# Main_Board.net
KiCad netlist of a schematic drawn in EAGLE
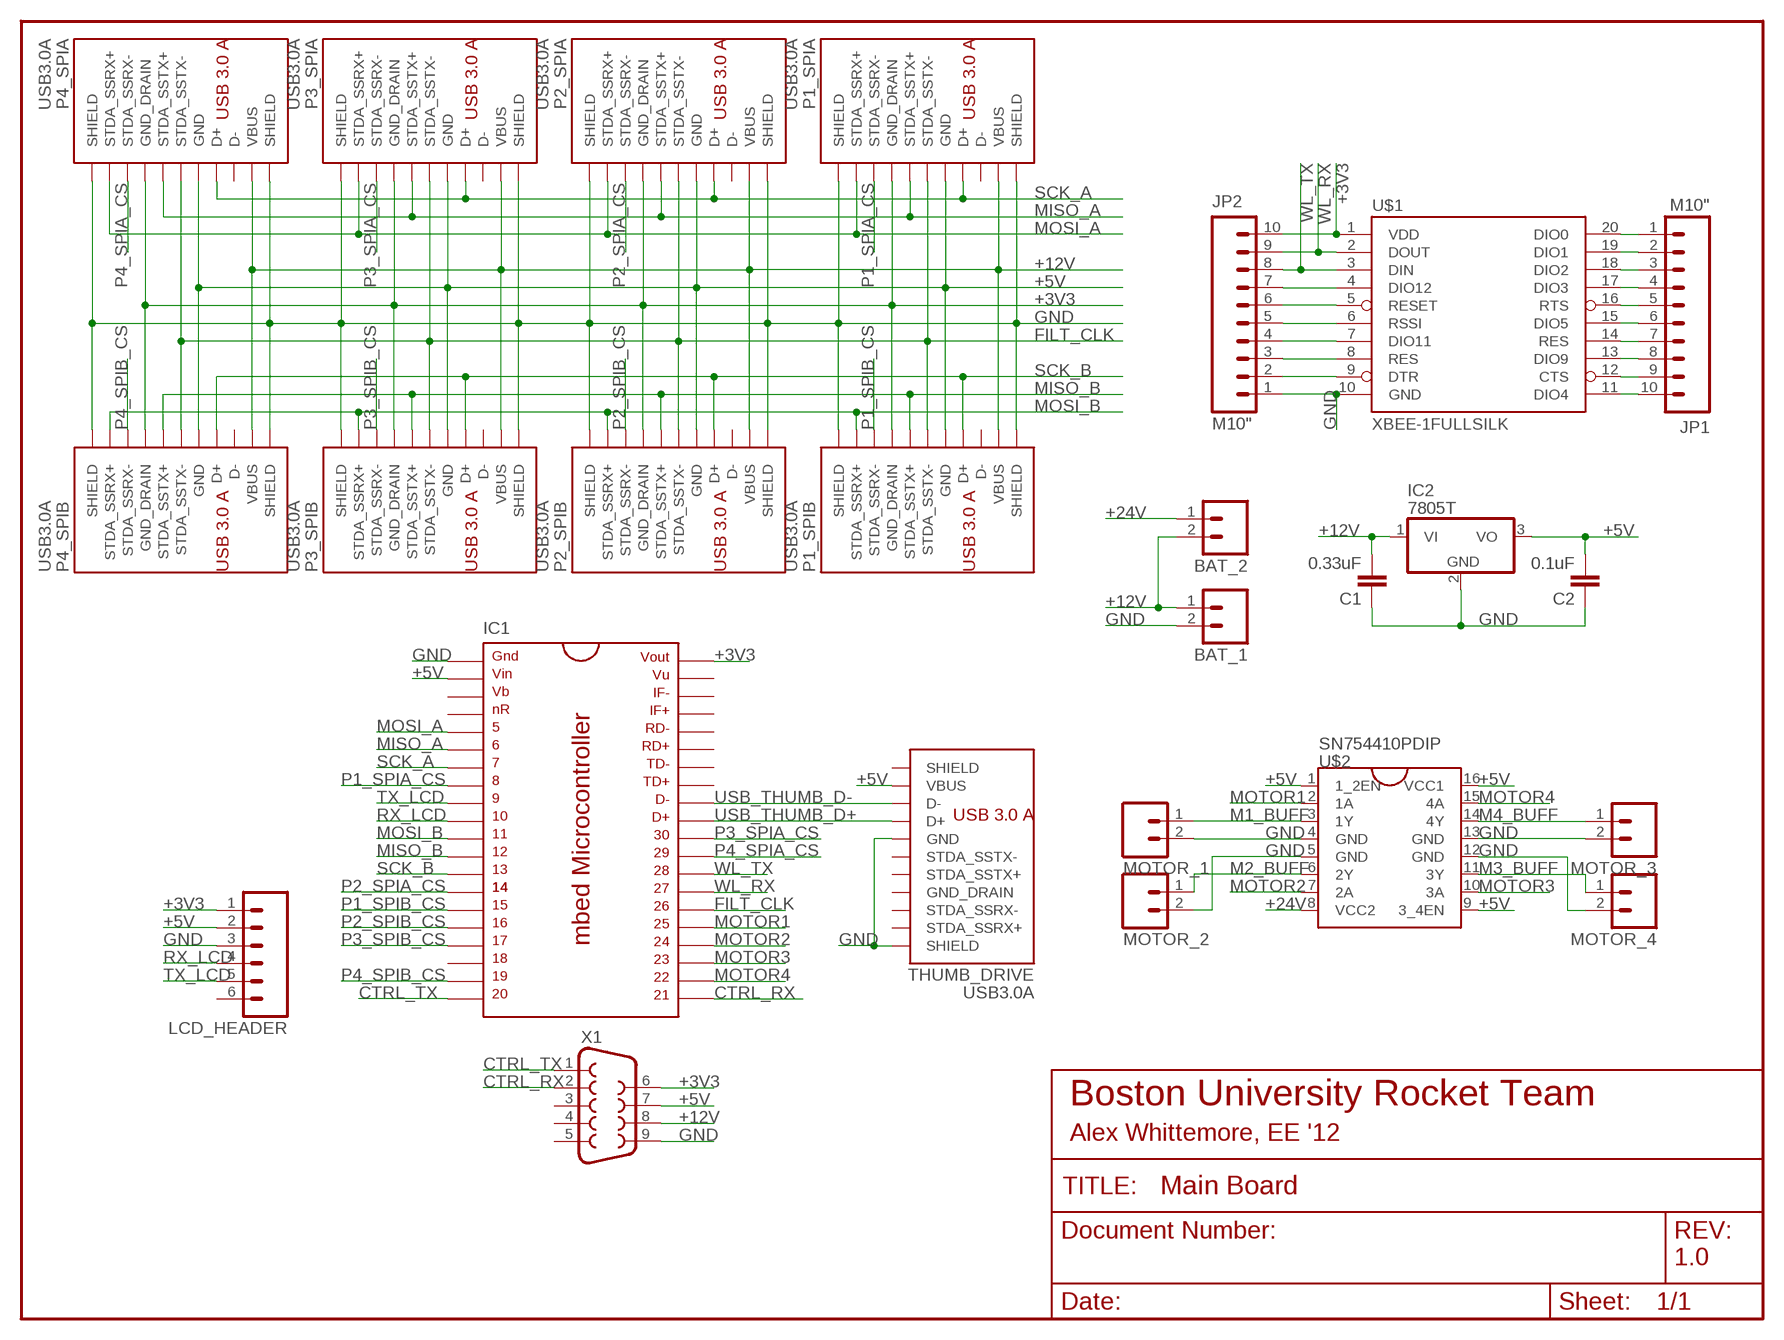
[diagram p0: schematic, sheet 1]

(export (version "E")
  (design (tool "Eeschema 10.0.6"))
  (components
    (comp (ref "BAT_1")
      (value "M025MM")
      (footprint "eagle-import:SCREWTERMINAL-5MM-2")
      (libsource (lib "eagle-import") (part "M025MM"))
    )
    (comp (ref "BAT_2")
      (value "M025MM")
      (footprint "eagle-import:SCREWTERMINAL-5MM-2")
      (libsource (lib "eagle-import") (part "M025MM"))
    )
    (comp (ref "C1")
      (value "0.33uF")
      (footprint "eagle-import:0402-CAP")
      (libsource (lib "eagle-import") (part "CAP0402-CAP"))
    )
    (comp (ref "C2")
      (value "0.1uF")
      (footprint "eagle-import:0402-CAP")
      (libsource (lib "eagle-import") (part "CAP0402-CAP"))
    )
    (comp (ref "IC1")
      (value "MBED_MICROCONTROLLER")
      (footprint "eagle-import:DIL40_0.9")
      (libsource (lib "eagle-import") (part "MBED_MICROCONTROLLER"))
    )
    (comp (ref "IC2")
      (value "7805T")
      (footprint "eagle-import:TO220H")
      (libsource (lib "eagle-import") (part "78T05"))
    )
    (comp (ref "JP1")
      (value "M10\"")
      (footprint "eagle-import:1X10")
      (libsource (lib "eagle-import") (part "M10{dblquote}"))
    )
    (comp (ref "JP2")
      (value "M10\"")
      (footprint "eagle-import:1X10")
      (libsource (lib "eagle-import") (part "M10{dblquote}"))
    )
    (comp (ref "LCD_HEADER")
      (value "M06LOCK")
      (footprint "eagle-import:1X06_LOCK")
      (libsource (lib "eagle-import") (part "M06LOCK"))
    )
    (comp (ref "MOTOR_1")
      (value "M025MM")
      (footprint "eagle-import:SCREWTERMINAL-5MM-2")
      (libsource (lib "eagle-import") (part "M025MM"))
    )
    (comp (ref "MOTOR_2")
      (value "M025MM")
      (footprint "eagle-import:SCREWTERMINAL-5MM-2")
      (libsource (lib "eagle-import") (part "M025MM"))
    )
    (comp (ref "MOTOR_3")
      (value "M025MM")
      (footprint "eagle-import:SCREWTERMINAL-5MM-2")
      (libsource (lib "eagle-import") (part "M025MM"))
    )
    (comp (ref "MOTOR_4")
      (value "M025MM")
      (footprint "eagle-import:SCREWTERMINAL-5MM-2")
      (libsource (lib "eagle-import") (part "M025MM"))
    )
    (comp (ref "P1_SPIA")
      (value "USB3.0A")
      (footprint "eagle-import:AMPHENOLUSB3.0A")
      (libsource (lib "eagle-import") (part "USB3.0A"))
    )
    (comp (ref "P1_SPIB")
      (value "USB3.0A")
      (footprint "eagle-import:AMPHENOLUSB3.0A")
      (libsource (lib "eagle-import") (part "USB3.0A"))
    )
    (comp (ref "P2_SPIA")
      (value "USB3.0A")
      (footprint "eagle-import:AMPHENOLUSB3.0A")
      (libsource (lib "eagle-import") (part "USB3.0A"))
    )
    (comp (ref "P2_SPIB")
      (value "USB3.0A")
      (footprint "eagle-import:AMPHENOLUSB3.0A")
      (libsource (lib "eagle-import") (part "USB3.0A"))
    )
    (comp (ref "P3_SPIA")
      (value "USB3.0A")
      (footprint "eagle-import:AMPHENOLUSB3.0A")
      (libsource (lib "eagle-import") (part "USB3.0A"))
    )
    (comp (ref "P3_SPIB")
      (value "USB3.0A")
      (footprint "eagle-import:AMPHENOLUSB3.0A")
      (libsource (lib "eagle-import") (part "USB3.0A"))
    )
    (comp (ref "P4_SPIA")
      (value "USB3.0A")
      (footprint "eagle-import:AMPHENOLUSB3.0A")
      (libsource (lib "eagle-import") (part "USB3.0A"))
    )
    (comp (ref "P4_SPIB")
      (value "USB3.0A")
      (footprint "eagle-import:AMPHENOLUSB3.0A")
      (libsource (lib "eagle-import") (part "USB3.0A"))
    )
    (comp (ref "THUMB_DRIVE")
      (value "USB3.0A")
      (footprint "eagle-import:AMPHENOLUSB3.0A")
      (libsource (lib "eagle-import") (part "USB3.0A"))
    )
    (comp (ref "U$1")
      (value "XBEE-1FULLSILK")
      (footprint "eagle-import:XBEE")
      (libsource (lib "eagle-import") (part "XBEE-1FULLSILK"))
    )
    (comp (ref "U$2")
      (value "SN754410PDIP")
      (footprint "eagle-import:DIL16")
      (libsource (lib "eagle-import") (part "SN754410PDIP"))
    )
    (comp (ref "X1")
      (value "DB9MALE")
      (footprint "eagle-import:DB9_MALE")
      (libsource (lib "eagle-import") (part "DB9MALE"))
    )
  )
  (nets
    (net (code "1") (name "/+3V3") (class "Default")
      (node (ref "IC1") (pin "40") (pinfunction "P$40_40") (pintype "bidirectional"))
      (node (ref "JP2") (pin "10") (pinfunction "10_10") (pintype "passive"))
      (node (ref "LCD_HEADER") (pin "1") (pinfunction "1_1") (pintype "passive"))
      (node (ref "P1_SPIA") (pin "7") (pinfunction "GND_DRAIN_7") (pintype "bidirectional"))
      (node (ref "P1_SPIB") (pin "7") (pinfunction "GND_DRAIN_7") (pintype "bidirectional"))
      (node (ref "P2_SPIA") (pin "7") (pinfunction "GND_DRAIN_7") (pintype "bidirectional"))
      (node (ref "P2_SPIB") (pin "7") (pinfunction "GND_DRAIN_7") (pintype "bidirectional"))
      (node (ref "P3_SPIA") (pin "7") (pinfunction "GND_DRAIN_7") (pintype "bidirectional"))
      (node (ref "P3_SPIB") (pin "7") (pinfunction "GND_DRAIN_7") (pintype "bidirectional"))
      (node (ref "P4_SPIA") (pin "7") (pinfunction "GND_DRAIN_7") (pintype "bidirectional"))
      (node (ref "P4_SPIB") (pin "7") (pinfunction "GND_DRAIN_7") (pintype "bidirectional"))
      (node (ref "U$1") (pin "1") (pinfunction "VDD_1") (pintype "power_in"))
      (node (ref "X1") (pin "6") (pinfunction "6_6") (pintype "passive"))
    )
    (net (code "2") (name "/+5V") (class "Default")
      (node (ref "C2") (pin "2") (pinfunction "2_2") (pintype "passive"))
      (node (ref "IC1") (pin "2") (pinfunction "P$2_2") (pintype "bidirectional"))
      (node (ref "IC2") (pin "3") (pinfunction "VO_3") (pintype "passive"))
      (node (ref "LCD_HEADER") (pin "2") (pinfunction "2_2") (pintype "passive"))
      (node (ref "P1_SPIA") (pin "4") (pinfunction "GND_4") (pintype "bidirectional"))
      (node (ref "P1_SPIB") (pin "4") (pinfunction "GND_4") (pintype "bidirectional"))
      (node (ref "P2_SPIA") (pin "4") (pinfunction "GND_4") (pintype "bidirectional"))
      (node (ref "P2_SPIB") (pin "4") (pinfunction "GND_4") (pintype "bidirectional"))
      (node (ref "P3_SPIA") (pin "4") (pinfunction "GND_4") (pintype "bidirectional"))
      (node (ref "P3_SPIB") (pin "4") (pinfunction "GND_4") (pintype "bidirectional"))
      (node (ref "P4_SPIA") (pin "4") (pinfunction "GND_4") (pintype "bidirectional"))
      (node (ref "P4_SPIB") (pin "4") (pinfunction "GND_4") (pintype "bidirectional"))
      (node (ref "THUMB_DRIVE") (pin "1") (pinfunction "VBUS_1") (pintype "bidirectional"))
      (node (ref "U$2") (pin "1") (pinfunction "1_2EN_1") (pintype "bidirectional"))
      (node (ref "U$2") (pin "16") (pinfunction "VCC1_16") (pintype "bidirectional"))
      (node (ref "U$2") (pin "9") (pinfunction "3_4EN_9") (pintype "bidirectional"))
      (node (ref "X1") (pin "7") (pinfunction "7_7") (pintype "passive"))
    )
    (net (code "3") (name "/+12V") (class "Default")
      (node (ref "BAT_1") (pin "1") (pinfunction "1_1") (pintype "passive"))
      (node (ref "BAT_2") (pin "2") (pinfunction "2_2") (pintype "passive"))
      (node (ref "C1") (pin "2") (pinfunction "2_2") (pintype "passive"))
      (node (ref "IC2") (pin "1") (pinfunction "VI_1") (pintype "input"))
      (node (ref "P1_SPIA") (pin "1") (pinfunction "VBUS_1") (pintype "bidirectional"))
      (node (ref "P1_SPIB") (pin "1") (pinfunction "VBUS_1") (pintype "bidirectional"))
      (node (ref "P2_SPIA") (pin "1") (pinfunction "VBUS_1") (pintype "bidirectional"))
      (node (ref "P2_SPIB") (pin "1") (pinfunction "VBUS_1") (pintype "bidirectional"))
      (node (ref "P3_SPIA") (pin "1") (pinfunction "VBUS_1") (pintype "bidirectional"))
      (node (ref "P3_SPIB") (pin "1") (pinfunction "VBUS_1") (pintype "bidirectional"))
      (node (ref "P4_SPIA") (pin "1") (pinfunction "VBUS_1") (pintype "bidirectional"))
      (node (ref "P4_SPIB") (pin "1") (pinfunction "VBUS_1") (pintype "bidirectional"))
      (node (ref "X1") (pin "8") (pinfunction "8_8") (pintype "passive"))
    )
    (net (code "4") (name "/+24V") (class "Default")
      (node (ref "BAT_2") (pin "1") (pinfunction "1_1") (pintype "passive"))
      (node (ref "U$2") (pin "8") (pinfunction "VCC2_8") (pintype "bidirectional"))
    )
    (net (code "5") (name "/CTRL_RX") (class "Default")
      (node (ref "IC1") (pin "21") (pinfunction "P$21_21") (pintype "bidirectional"))
      (node (ref "X1") (pin "2") (pinfunction "2_2") (pintype "passive"))
    )
    (net (code "6") (name "/CTRL_TX") (class "Default")
      (node (ref "IC1") (pin "20") (pinfunction "P$20_20") (pintype "bidirectional"))
      (node (ref "X1") (pin "1") (pinfunction "1_1") (pintype "passive"))
    )
    (net (code "7") (name "/FILT_CLK") (class "Default")
      (node (ref "IC1") (pin "26") (pinfunction "P$26_26") (pintype "bidirectional"))
      (node (ref "P1_SPIA") (pin "8") (pinfunction "STDA_SSTX-_8") (pintype "bidirectional"))
      (node (ref "P1_SPIB") (pin "8") (pinfunction "STDA_SSTX-_8") (pintype "bidirectional"))
      (node (ref "P2_SPIA") (pin "8") (pinfunction "STDA_SSTX-_8") (pintype "bidirectional"))
      (node (ref "P2_SPIB") (pin "8") (pinfunction "STDA_SSTX-_8") (pintype "bidirectional"))
      (node (ref "P3_SPIA") (pin "8") (pinfunction "STDA_SSTX-_8") (pintype "bidirectional"))
      (node (ref "P3_SPIB") (pin "8") (pinfunction "STDA_SSTX-_8") (pintype "bidirectional"))
      (node (ref "P4_SPIA") (pin "8") (pinfunction "STDA_SSTX-_8") (pintype "bidirectional"))
      (node (ref "P4_SPIB") (pin "8") (pinfunction "STDA_SSTX-_8") (pintype "bidirectional"))
    )
    (net (code "8") (name "/GND") (class "Default")
      (node (ref "BAT_1") (pin "2") (pinfunction "2_2") (pintype "passive"))
      (node (ref "C1") (pin "1") (pinfunction "1_1") (pintype "passive"))
      (node (ref "C2") (pin "1") (pinfunction "1_1") (pintype "passive"))
      (node (ref "IC1") (pin "1") (pinfunction "P$1_1") (pintype "bidirectional"))
      (node (ref "IC2") (pin "2") (pinfunction "GND_2") (pintype "passive"))
      (node (ref "JP2") (pin "1") (pinfunction "1_1") (pintype "passive"))
      (node (ref "LCD_HEADER") (pin "3") (pinfunction "3_3") (pintype "passive"))
      (node (ref "MOTOR_1") (pin "2") (pinfunction "2_2") (pintype "passive"))
      (node (ref "MOTOR_2") (pin "2") (pinfunction "2_2") (pintype "passive"))
      (node (ref "MOTOR_3") (pin "2") (pinfunction "2_2") (pintype "passive"))
      (node (ref "MOTOR_4") (pin "2") (pinfunction "2_2") (pintype "passive"))
      (node (ref "P1_SPIA") (pin "10@1") (pinfunction "SHIELD_10@1") (pintype "bidirectional"))
      (node (ref "P1_SPIA") (pin "10@2") (pinfunction "SHIELD_10@2") (pintype "bidirectional"))
      (node (ref "P1_SPIB") (pin "10@1") (pinfunction "SHIELD_10@1") (pintype "bidirectional"))
      (node (ref "P1_SPIB") (pin "10@2") (pinfunction "SHIELD_10@2") (pintype "bidirectional"))
      (node (ref "P2_SPIA") (pin "10@1") (pinfunction "SHIELD_10@1") (pintype "bidirectional"))
      (node (ref "P2_SPIA") (pin "10@2") (pinfunction "SHIELD_10@2") (pintype "bidirectional"))
      (node (ref "P2_SPIB") (pin "10@1") (pinfunction "SHIELD_10@1") (pintype "bidirectional"))
      (node (ref "P2_SPIB") (pin "10@2") (pinfunction "SHIELD_10@2") (pintype "bidirectional"))
      (node (ref "P3_SPIA") (pin "10@1") (pinfunction "SHIELD_10@1") (pintype "bidirectional"))
      (node (ref "P3_SPIA") (pin "10@2") (pinfunction "SHIELD_10@2") (pintype "bidirectional"))
      (node (ref "P3_SPIB") (pin "10@1") (pinfunction "SHIELD_10@1") (pintype "bidirectional"))
      (node (ref "P3_SPIB") (pin "10@2") (pinfunction "SHIELD_10@2") (pintype "bidirectional"))
      (node (ref "P4_SPIA") (pin "10@1") (pinfunction "SHIELD_10@1") (pintype "bidirectional"))
      (node (ref "P4_SPIA") (pin "10@2") (pinfunction "SHIELD_10@2") (pintype "bidirectional"))
      (node (ref "P4_SPIB") (pin "10@1") (pinfunction "SHIELD_10@1") (pintype "bidirectional"))
      (node (ref "P4_SPIB") (pin "10@2") (pinfunction "SHIELD_10@2") (pintype "bidirectional"))
      (node (ref "THUMB_DRIVE") (pin "10@2") (pinfunction "SHIELD_10@2") (pintype "bidirectional"))
      (node (ref "THUMB_DRIVE") (pin "4") (pinfunction "GND_4") (pintype "bidirectional"))
      (node (ref "U$1") (pin "10") (pinfunction "GND_10") (pintype "power_in"))
      (node (ref "U$2") (pin "12") (pinfunction "GND_12") (pintype "bidirectional"))
      (node (ref "U$2") (pin "13") (pinfunction "GND_13") (pintype "bidirectional"))
      (node (ref "U$2") (pin "4") (pinfunction "GND_4") (pintype "bidirectional"))
      (node (ref "U$2") (pin "5") (pinfunction "GND_5") (pintype "bidirectional"))
      (node (ref "X1") (pin "9") (pinfunction "9_9") (pintype "passive"))
    )
    (net (code "9") (name "/M1_BUFF") (class "Default")
      (node (ref "MOTOR_1") (pin "1") (pinfunction "1_1") (pintype "passive"))
      (node (ref "U$2") (pin "3") (pinfunction "1Y_3") (pintype "bidirectional"))
    )
    (net (code "10") (name "/M2_BUFF") (class "Default")
      (node (ref "MOTOR_2") (pin "1") (pinfunction "1_1") (pintype "passive"))
      (node (ref "U$2") (pin "6") (pinfunction "2Y_6") (pintype "bidirectional"))
    )
    (net (code "11") (name "/M3_BUFF") (class "Default")
      (node (ref "MOTOR_4") (pin "1") (pinfunction "1_1") (pintype "passive"))
      (node (ref "U$2") (pin "11") (pinfunction "3Y_11") (pintype "bidirectional"))
    )
    (net (code "12") (name "/M4_BUFF") (class "Default")
      (node (ref "MOTOR_3") (pin "1") (pinfunction "1_1") (pintype "passive"))
      (node (ref "U$2") (pin "14") (pinfunction "4Y_14") (pintype "bidirectional"))
    )
    (net (code "13") (name "/MISO_A") (class "Default")
      (node (ref "IC1") (pin "6") (pinfunction "P$6_6") (pintype "bidirectional"))
      (node (ref "P1_SPIA") (pin "9") (pinfunction "STDA_SSTX+_9") (pintype "bidirectional"))
      (node (ref "P2_SPIA") (pin "9") (pinfunction "STDA_SSTX+_9") (pintype "bidirectional"))
      (node (ref "P3_SPIA") (pin "9") (pinfunction "STDA_SSTX+_9") (pintype "bidirectional"))
      (node (ref "P4_SPIA") (pin "9") (pinfunction "STDA_SSTX+_9") (pintype "bidirectional"))
    )
    (net (code "14") (name "/MISO_B") (class "Default")
      (node (ref "IC1") (pin "12") (pinfunction "P$12_12") (pintype "bidirectional"))
      (node (ref "P1_SPIB") (pin "9") (pinfunction "STDA_SSTX+_9") (pintype "bidirectional"))
      (node (ref "P2_SPIB") (pin "9") (pinfunction "STDA_SSTX+_9") (pintype "bidirectional"))
      (node (ref "P3_SPIB") (pin "9") (pinfunction "STDA_SSTX+_9") (pintype "bidirectional"))
      (node (ref "P4_SPIB") (pin "9") (pinfunction "STDA_SSTX+_9") (pintype "bidirectional"))
    )
    (net (code "15") (name "/MOSI_A") (class "Default")
      (node (ref "IC1") (pin "5") (pinfunction "P$5_5") (pintype "bidirectional"))
      (node (ref "P1_SPIA") (pin "6") (pinfunction "STDA_SSRX+_6") (pintype "bidirectional"))
      (node (ref "P2_SPIA") (pin "6") (pinfunction "STDA_SSRX+_6") (pintype "bidirectional"))
      (node (ref "P3_SPIA") (pin "6") (pinfunction "STDA_SSRX+_6") (pintype "bidirectional"))
      (node (ref "P4_SPIA") (pin "6") (pinfunction "STDA_SSRX+_6") (pintype "bidirectional"))
    )
    (net (code "16") (name "/MOSI_B") (class "Default")
      (node (ref "IC1") (pin "11") (pinfunction "P$11_11") (pintype "bidirectional"))
      (node (ref "P1_SPIB") (pin "6") (pinfunction "STDA_SSRX+_6") (pintype "bidirectional"))
      (node (ref "P2_SPIB") (pin "6") (pinfunction "STDA_SSRX+_6") (pintype "bidirectional"))
      (node (ref "P3_SPIB") (pin "6") (pinfunction "STDA_SSRX+_6") (pintype "bidirectional"))
      (node (ref "P4_SPIB") (pin "6") (pinfunction "STDA_SSRX+_6") (pintype "bidirectional"))
    )
    (net (code "17") (name "/MOTOR1") (class "Default")
      (node (ref "IC1") (pin "25") (pinfunction "P$25_25") (pintype "bidirectional"))
      (node (ref "U$2") (pin "2") (pinfunction "1A_2") (pintype "bidirectional"))
    )
    (net (code "18") (name "/MOTOR2") (class "Default")
      (node (ref "IC1") (pin "24") (pinfunction "P$24_24") (pintype "bidirectional"))
      (node (ref "U$2") (pin "7") (pinfunction "2A_7") (pintype "bidirectional"))
    )
    (net (code "19") (name "/MOTOR3") (class "Default")
      (node (ref "IC1") (pin "23") (pinfunction "P$23_23") (pintype "bidirectional"))
      (node (ref "U$2") (pin "10") (pinfunction "3A_10") (pintype "bidirectional"))
    )
    (net (code "20") (name "/MOTOR4") (class "Default")
      (node (ref "IC1") (pin "22") (pinfunction "P$22_22") (pintype "bidirectional"))
      (node (ref "U$2") (pin "15") (pinfunction "4A_15") (pintype "bidirectional"))
    )
    (net (code "21") (name "/P1_SPIA_CS") (class "Default")
      (node (ref "IC1") (pin "8") (pinfunction "P$8_8") (pintype "bidirectional"))
      (node (ref "P1_SPIA") (pin "5") (pinfunction "STDA_SSRX-_5") (pintype "bidirectional"))
    )
    (net (code "22") (name "/P1_SPIB_CS") (class "Default")
      (node (ref "IC1") (pin "15") (pinfunction "P$15_15") (pintype "bidirectional"))
      (node (ref "P1_SPIB") (pin "5") (pinfunction "STDA_SSRX-_5") (pintype "bidirectional"))
    )
    (net (code "23") (name "/P2_SPIA_CS") (class "Default")
      (node (ref "IC1") (pin "14") (pinfunction "P$14_14") (pintype "bidirectional"))
      (node (ref "P2_SPIA") (pin "5") (pinfunction "STDA_SSRX-_5") (pintype "bidirectional"))
    )
    (net (code "24") (name "/P2_SPIB_CS") (class "Default")
      (node (ref "IC1") (pin "16") (pinfunction "P$16_16") (pintype "bidirectional"))
      (node (ref "P2_SPIB") (pin "5") (pinfunction "STDA_SSRX-_5") (pintype "bidirectional"))
    )
    (net (code "25") (name "/P3_SPIA_CS") (class "Default")
      (node (ref "IC1") (pin "30") (pinfunction "P$30_30") (pintype "bidirectional"))
      (node (ref "P3_SPIA") (pin "5") (pinfunction "STDA_SSRX-_5") (pintype "bidirectional"))
    )
    (net (code "26") (name "/P3_SPIB_CS") (class "Default")
      (node (ref "IC1") (pin "17") (pinfunction "P$17_17") (pintype "bidirectional"))
      (node (ref "P3_SPIB") (pin "5") (pinfunction "STDA_SSRX-_5") (pintype "bidirectional"))
    )
    (net (code "27") (name "/P4_SPIA_CS") (class "Default")
      (node (ref "IC1") (pin "29") (pinfunction "P$29_29") (pintype "bidirectional"))
      (node (ref "P4_SPIA") (pin "5") (pinfunction "STDA_SSRX-_5") (pintype "bidirectional"))
    )
    (net (code "28") (name "/P4_SPIB_CS") (class "Default")
      (node (ref "IC1") (pin "19") (pinfunction "P$19_19") (pintype "bidirectional"))
      (node (ref "P4_SPIB") (pin "5") (pinfunction "STDA_SSRX-_5") (pintype "bidirectional"))
    )
    (net (code "29") (name "/RX_LCD") (class "Default")
      (node (ref "IC1") (pin "10") (pinfunction "P$10_10") (pintype "bidirectional"))
      (node (ref "LCD_HEADER") (pin "4") (pinfunction "4_4") (pintype "passive"))
    )
    (net (code "30") (name "/SCK_A") (class "Default")
      (node (ref "IC1") (pin "7") (pinfunction "P$7_7") (pintype "bidirectional"))
      (node (ref "P1_SPIA") (pin "3") (pinfunction "D+_3") (pintype "bidirectional"))
      (node (ref "P2_SPIA") (pin "3") (pinfunction "D+_3") (pintype "bidirectional"))
      (node (ref "P3_SPIA") (pin "3") (pinfunction "D+_3") (pintype "bidirectional"))
      (node (ref "P4_SPIA") (pin "3") (pinfunction "D+_3") (pintype "bidirectional"))
    )
    (net (code "31") (name "/SCK_B") (class "Default")
      (node (ref "IC1") (pin "13") (pinfunction "P$13_13") (pintype "bidirectional"))
      (node (ref "P1_SPIB") (pin "3") (pinfunction "D+_3") (pintype "bidirectional"))
      (node (ref "P2_SPIB") (pin "3") (pinfunction "D+_3") (pintype "bidirectional"))
      (node (ref "P3_SPIB") (pin "3") (pinfunction "D+_3") (pintype "bidirectional"))
      (node (ref "P4_SPIB") (pin "3") (pinfunction "D+_3") (pintype "bidirectional"))
    )
    (net (code "32") (name "/TX_LCD") (class "Default")
      (node (ref "IC1") (pin "9") (pinfunction "P$9_9") (pintype "bidirectional"))
      (node (ref "LCD_HEADER") (pin "5") (pinfunction "5_5") (pintype "passive"))
    )
    (net (code "33") (name "/USB_THUMB_D+") (class "Default")
      (node (ref "IC1") (pin "31") (pinfunction "P$31_31") (pintype "bidirectional"))
      (node (ref "THUMB_DRIVE") (pin "3") (pinfunction "D+_3") (pintype "bidirectional"))
    )
    (net (code "34") (name "/USB_THUMB_D-") (class "Default")
      (node (ref "IC1") (pin "32") (pinfunction "P$32_32") (pintype "bidirectional"))
      (node (ref "THUMB_DRIVE") (pin "2") (pinfunction "D-_2") (pintype "bidirectional"))
    )
    (net (code "35") (name "/WL_RX") (class "Default")
      (node (ref "IC1") (pin "27") (pinfunction "P$27_27") (pintype "bidirectional"))
      (node (ref "JP2") (pin "9") (pinfunction "9_9") (pintype "passive"))
      (node (ref "U$1") (pin "2") (pinfunction "DOUT_2") (pintype "output"))
    )
    (net (code "36") (name "/WL_TX") (class "Default")
      (node (ref "IC1") (pin "28") (pinfunction "P$28_28") (pintype "bidirectional"))
      (node (ref "JP2") (pin "8") (pinfunction "8_8") (pintype "passive"))
      (node (ref "U$1") (pin "3") (pinfunction "DIN_3") (pintype "input"))
    )
    (net (code "37") (name "Net-(JP1-Pad7)") (class "Default")
      (node (ref "JP1") (pin "7") (pinfunction "7_7") (pintype "passive"))
      (node (ref "U$1") (pin "14") (pinfunction "RES_14") (pintype "bidirectional"))
    )
    (net (code "38") (name "Net-(JP2-Pad3)") (class "Default")
      (node (ref "JP2") (pin "3") (pinfunction "3_3") (pintype "passive"))
      (node (ref "U$1") (pin "8") (pinfunction "RES_8") (pintype "bidirectional"))
    )
    (net (code "39") (name "Net-(U$1-CTS)") (class "Default")
      (node (ref "JP1") (pin "9") (pinfunction "9_9") (pintype "passive"))
      (node (ref "U$1") (pin "12") (pinfunction "CTS_12") (pintype "output"))
    )
    (net (code "40") (name "Net-(U$1-DIO0)") (class "Default")
      (node (ref "JP1") (pin "1") (pinfunction "1_1") (pintype "passive"))
      (node (ref "U$1") (pin "20") (pinfunction "DIO0_20") (pintype "bidirectional"))
    )
    (net (code "41") (name "Net-(U$1-DIO1)") (class "Default")
      (node (ref "JP1") (pin "2") (pinfunction "2_2") (pintype "passive"))
      (node (ref "U$1") (pin "19") (pinfunction "DIO1_19") (pintype "bidirectional"))
    )
    (net (code "42") (name "Net-(U$1-DIO2)") (class "Default")
      (node (ref "JP1") (pin "3") (pinfunction "3_3") (pintype "passive"))
      (node (ref "U$1") (pin "18") (pinfunction "DIO2_18") (pintype "bidirectional"))
    )
    (net (code "43") (name "Net-(U$1-DIO3)") (class "Default")
      (node (ref "JP1") (pin "4") (pinfunction "4_4") (pintype "passive"))
      (node (ref "U$1") (pin "17") (pinfunction "DIO3_17") (pintype "bidirectional"))
    )
    (net (code "44") (name "Net-(U$1-DIO4)") (class "Default")
      (node (ref "JP1") (pin "10") (pinfunction "10_10") (pintype "passive"))
      (node (ref "U$1") (pin "11") (pinfunction "DIO4_11") (pintype "bidirectional"))
    )
    (net (code "45") (name "Net-(U$1-DIO5)") (class "Default")
      (node (ref "JP1") (pin "6") (pinfunction "6_6") (pintype "passive"))
      (node (ref "U$1") (pin "15") (pinfunction "DIO5_15") (pintype "bidirectional"))
    )
    (net (code "46") (name "Net-(U$1-DIO9)") (class "Default")
      (node (ref "JP1") (pin "8") (pinfunction "8_8") (pintype "passive"))
      (node (ref "U$1") (pin "13") (pinfunction "DIO9_13") (pintype "bidirectional"))
    )
    (net (code "47") (name "Net-(U$1-DIO11)") (class "Default")
      (node (ref "JP2") (pin "4") (pinfunction "4_4") (pintype "passive"))
      (node (ref "U$1") (pin "7") (pinfunction "DIO11_7") (pintype "bidirectional"))
    )
    (net (code "48") (name "Net-(U$1-DIO12)") (class "Default")
      (node (ref "JP2") (pin "7") (pinfunction "7_7") (pintype "passive"))
      (node (ref "U$1") (pin "4") (pinfunction "DIO12_4") (pintype "bidirectional"))
    )
    (net (code "49") (name "Net-(U$1-DTR)") (class "Default")
      (node (ref "JP2") (pin "2") (pinfunction "2_2") (pintype "passive"))
      (node (ref "U$1") (pin "9") (pinfunction "DTR_9") (pintype "bidirectional"))
    )
    (net (code "50") (name "Net-(U$1-RESET)") (class "Default")
      (node (ref "JP2") (pin "6") (pinfunction "6_6") (pintype "passive"))
      (node (ref "U$1") (pin "5") (pinfunction "RESET_5") (pintype "input"))
    )
    (net (code "51") (name "Net-(U$1-RSSI)") (class "Default")
      (node (ref "JP2") (pin "5") (pinfunction "5_5") (pintype "passive"))
      (node (ref "U$1") (pin "6") (pinfunction "RSSI_6") (pintype "bidirectional"))
    )
    (net (code "52") (name "Net-(U$1-RTS)") (class "Default")
      (node (ref "JP1") (pin "5") (pinfunction "5_5") (pintype "passive"))
      (node (ref "U$1") (pin "16") (pinfunction "RTS_16") (pintype "input"))
    )
    (net (code "53") (name "unconnected-(IC1-P$3-Pad3)") (class "Default")
      (node (ref "IC1") (pin "3") (pinfunction "P$3_3") (pintype "bidirectional"))
    )
    (net (code "54") (name "unconnected-(IC1-P$4-Pad4)") (class "Default")
      (node (ref "IC1") (pin "4") (pinfunction "P$4_4") (pintype "bidirectional"))
    )
    (net (code "55") (name "unconnected-(IC1-P$18-Pad18)") (class "Default")
      (node (ref "IC1") (pin "18") (pinfunction "P$18_18") (pintype "bidirectional"))
    )
    (net (code "56") (name "unconnected-(IC1-P$33-Pad33)") (class "Default")
      (node (ref "IC1") (pin "33") (pinfunction "P$33_33") (pintype "bidirectional"))
    )
    (net (code "57") (name "unconnected-(IC1-P$34-Pad34)") (class "Default")
      (node (ref "IC1") (pin "34") (pinfunction "P$34_34") (pintype "bidirectional"))
    )
    (net (code "58") (name "unconnected-(IC1-P$35-Pad35)") (class "Default")
      (node (ref "IC1") (pin "35") (pinfunction "P$35_35") (pintype "bidirectional"))
    )
    (net (code "59") (name "unconnected-(IC1-P$36-Pad36)") (class "Default")
      (node (ref "IC1") (pin "36") (pinfunction "P$36_36") (pintype "bidirectional"))
    )
    (net (code "60") (name "unconnected-(IC1-P$37-Pad37)") (class "Default")
      (node (ref "IC1") (pin "37") (pinfunction "P$37_37") (pintype "bidirectional"))
    )
    (net (code "61") (name "unconnected-(IC1-P$38-Pad38)") (class "Default")
      (node (ref "IC1") (pin "38") (pinfunction "P$38_38") (pintype "bidirectional"))
    )
    (net (code "62") (name "unconnected-(IC1-P$39-Pad39)") (class "Default")
      (node (ref "IC1") (pin "39") (pinfunction "P$39_39") (pintype "bidirectional"))
    )
    (net (code "63") (name "unconnected-(LCD_HEADER-Pad6)") (class "Default")
      (node (ref "LCD_HEADER") (pin "6") (pinfunction "6_6") (pintype "passive"))
    )
    (net (code "64") (name "unconnected-(P1_SPIA-D--Pad2)") (class "Default")
      (node (ref "P1_SPIA") (pin "2") (pinfunction "D-_2") (pintype "bidirectional"))
    )
    (net (code "65") (name "unconnected-(P1_SPIB-D--Pad2)") (class "Default")
      (node (ref "P1_SPIB") (pin "2") (pinfunction "D-_2") (pintype "bidirectional"))
    )
    (net (code "66") (name "unconnected-(P2_SPIA-D--Pad2)") (class "Default")
      (node (ref "P2_SPIA") (pin "2") (pinfunction "D-_2") (pintype "bidirectional"))
    )
    (net (code "67") (name "unconnected-(P2_SPIB-D--Pad2)") (class "Default")
      (node (ref "P2_SPIB") (pin "2") (pinfunction "D-_2") (pintype "bidirectional"))
    )
    (net (code "68") (name "unconnected-(P3_SPIA-D--Pad2)") (class "Default")
      (node (ref "P3_SPIA") (pin "2") (pinfunction "D-_2") (pintype "bidirectional"))
    )
    (net (code "69") (name "unconnected-(P3_SPIB-D--Pad2)") (class "Default")
      (node (ref "P3_SPIB") (pin "2") (pinfunction "D-_2") (pintype "bidirectional"))
    )
    (net (code "70") (name "unconnected-(P4_SPIA-D--Pad2)") (class "Default")
      (node (ref "P4_SPIA") (pin "2") (pinfunction "D-_2") (pintype "bidirectional"))
    )
    (net (code "71") (name "unconnected-(P4_SPIB-D--Pad2)") (class "Default")
      (node (ref "P4_SPIB") (pin "2") (pinfunction "D-_2") (pintype "bidirectional"))
    )
    (net (code "72") (name "unconnected-(THUMB_DRIVE-GND_DRAIN-Pad7)") (class "Default")
      (node (ref "THUMB_DRIVE") (pin "7") (pinfunction "GND_DRAIN_7") (pintype "bidirectional"))
    )
    (net (code "73") (name "unconnected-(THUMB_DRIVE-SHIELD-Pad10@1)") (class "Default")
      (node (ref "THUMB_DRIVE") (pin "10@1") (pinfunction "SHIELD_10@1") (pintype "bidirectional"))
    )
    (net (code "74") (name "unconnected-(THUMB_DRIVE-STDA_SSRX+-Pad6)") (class "Default")
      (node (ref "THUMB_DRIVE") (pin "6") (pinfunction "STDA_SSRX+_6") (pintype "bidirectional"))
    )
    (net (code "75") (name "unconnected-(THUMB_DRIVE-STDA_SSRX--Pad5)") (class "Default")
      (node (ref "THUMB_DRIVE") (pin "5") (pinfunction "STDA_SSRX-_5") (pintype "bidirectional"))
    )
    (net (code "76") (name "unconnected-(THUMB_DRIVE-STDA_SSTX+-Pad9)") (class "Default")
      (node (ref "THUMB_DRIVE") (pin "9") (pinfunction "STDA_SSTX+_9") (pintype "bidirectional"))
    )
    (net (code "77") (name "unconnected-(THUMB_DRIVE-STDA_SSTX--Pad8)") (class "Default")
      (node (ref "THUMB_DRIVE") (pin "8") (pinfunction "STDA_SSTX-_8") (pintype "bidirectional"))
    )
    (net (code "78") (name "unconnected-(X1-Pad3)") (class "Default")
      (node (ref "X1") (pin "3") (pinfunction "3_3") (pintype "passive"))
    )
    (net (code "79") (name "unconnected-(X1-Pad4)") (class "Default")
      (node (ref "X1") (pin "4") (pinfunction "4_4") (pintype "passive"))
    )
    (net (code "80") (name "unconnected-(X1-Pad5)") (class "Default")
      (node (ref "X1") (pin "5") (pinfunction "5_5") (pintype "passive"))
    )
  )
)
